# LED_Controller.net
KiCad netlist of a schematic drawn in Altium Designer
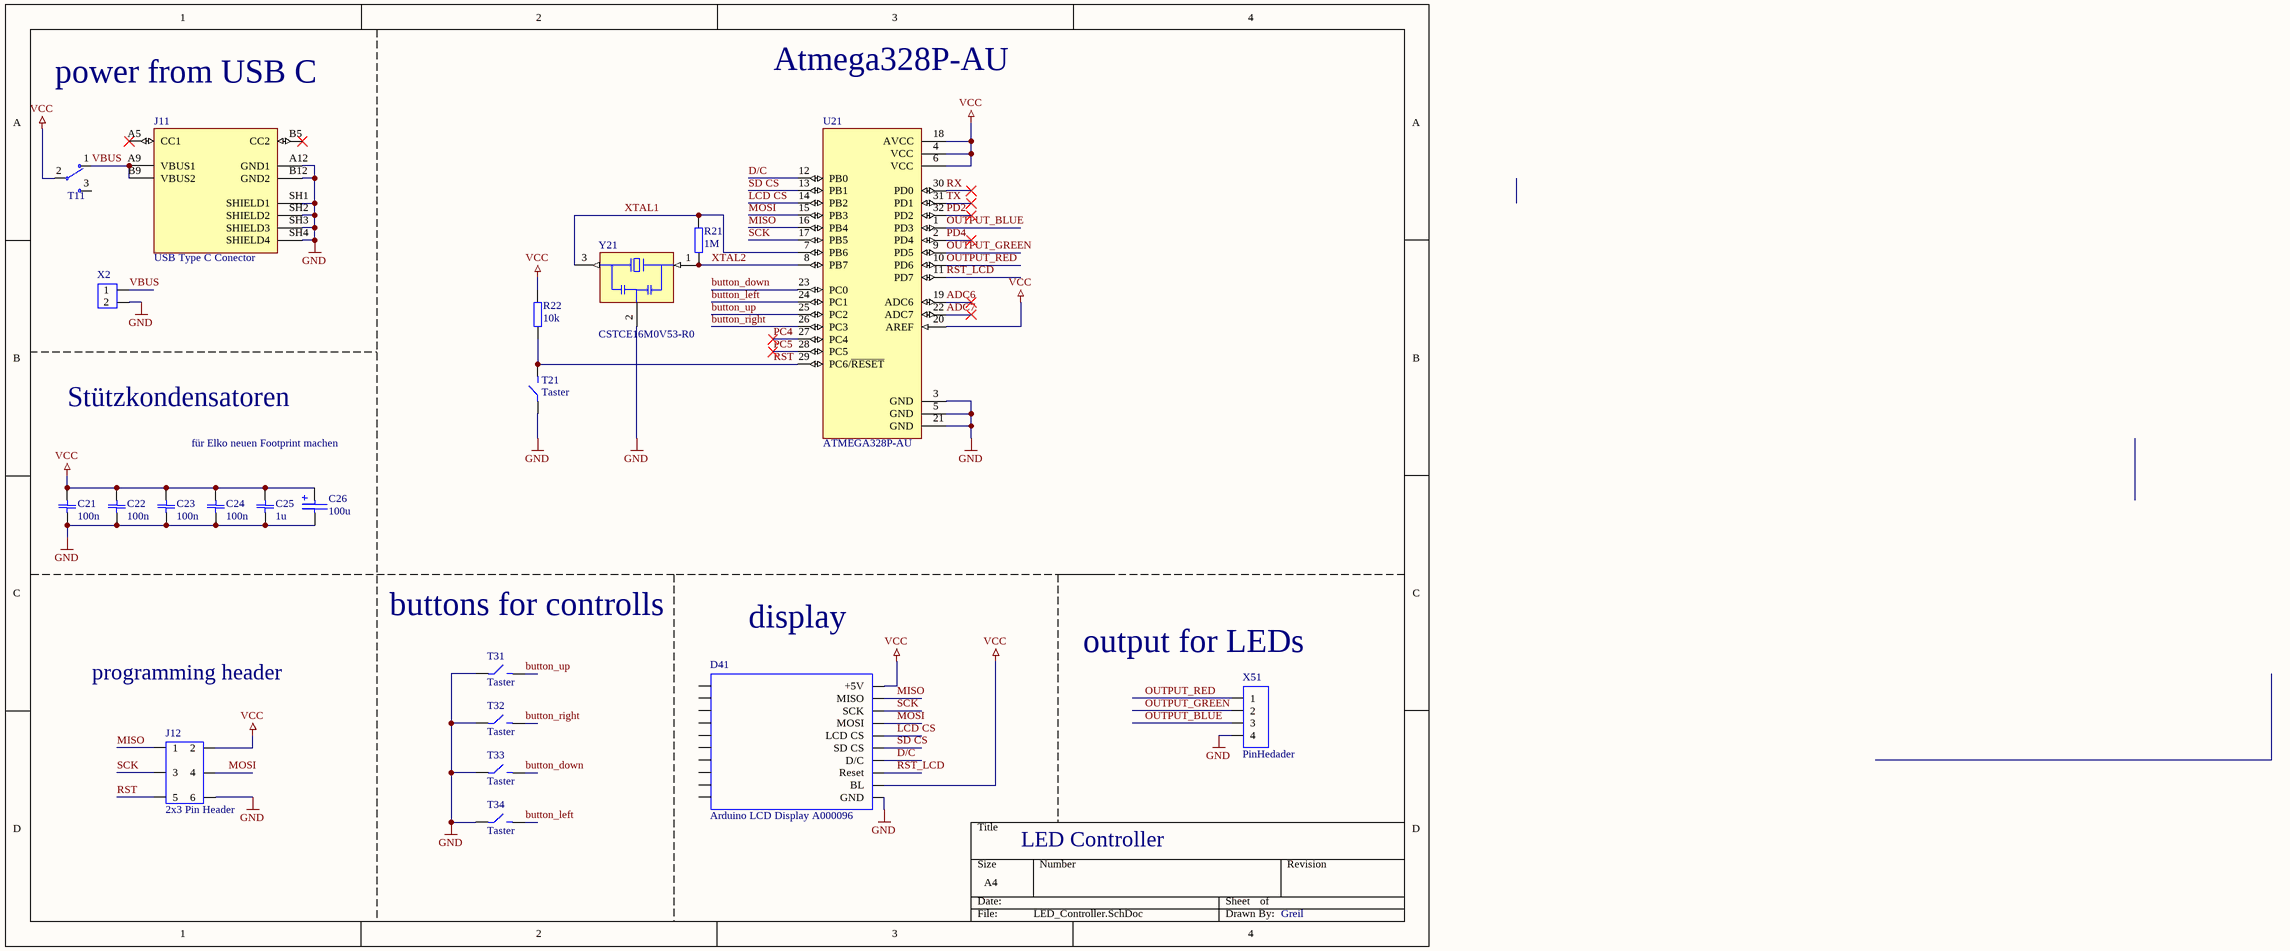
[diagram p0: LED_Controller.SchDoc]

(export (version "E")
  (design (tool "Eeschema 10.0.6"))
  (components
    (comp (ref "C21")
      (value "100n")
      (footprint "CAP0805")
      (fields (field (name "MP") "VJ1206A220GXCAP"))
      (libsource (lib "LED_Controller") (part "SMD CAP"))
    )
    (comp (ref "C22")
      (value "100n")
      (footprint "CAP0805")
      (fields (field (name "MP") "VJ1206A220GXCAP"))
      (libsource (lib "LED_Controller") (part "SMD CAP"))
    )
    (comp (ref "C23")
      (value "100n")
      (footprint "CAP0805")
      (fields (field (name "MP") "VJ1206A220GXCAP"))
      (libsource (lib "LED_Controller") (part "SMD CAP"))
    )
    (comp (ref "C24")
      (value "100n")
      (footprint "CAP0805")
      (fields (field (name "MP") "VJ1206A220GXCAP"))
      (libsource (lib "LED_Controller") (part "SMD CAP"))
    )
    (comp (ref "C25")
      (value "1u")
      (footprint "CAP0805")
      (fields (field (name "MP") "VJ1206A220GXCAP"))
      (libsource (lib "LED_Controller") (part "SMD CAP"))
    )
    (comp (ref "C26") (value "100u") (footprint "ELKO_D5.0") (libsource (lib "1BHELS_2_Greil") (part "ELKO")))
    (comp (ref "D41")
      (value "Arduino LCD Display A000096")
      (footprint "Arduino LCD Display A000096")
      (libsource (lib "1BHELS_2_Greil") (part "Arduino LCD Display A000096"))
    )
    (comp (ref "J11")
      (value "USB Type C Conector")
      (footprint "MOLEX_2171750001")
      (fields (field (name "MF") "Molex") (field (name "MP") "2171750001"))
      (libsource (lib "LED_Controller") (part "USB Type C Conector"))
    )
    (comp (ref "J12")
      (value "2x3 Pin Header")
      (footprint "2x3 Pin Header")
      (libsource (lib "LED_Controller") (part "2x3 Pin Header"))
    )
    (comp (ref "R21")
      (value "1M")
      (footprint "LED_Controller:RES_ERJU08J154V")
      (fields (field (name "MP") "ERJU08J154V"))
      (libsource (lib "LED_Controller") (part "Res 1206"))
    )
    (comp (ref "R22")
      (value "10k")
      (footprint "LED_Controller:RES_ERJU08J154V")
      (fields (field (name "MP") "ERJU08J154V"))
      (libsource (lib "LED_Controller") (part "Res 1206"))
    )
    (comp (ref "T11")
      (value "Toggel Switch")
      (footprint "Toggel Switch")
      (libsource (lib "LED_Controller") (part "Toggel Switch"))
    )
    (comp (ref "T21")
      (value "Taster")
      (footprint "Taster")
      (libsource (lib "1BHELS_2_Greil") (part "Taster"))
    )
    (comp (ref "T31")
      (value "Taster")
      (footprint "Taster")
      (libsource (lib "1BHELS_2_Greil") (part "Taster"))
    )
    (comp (ref "T32")
      (value "Taster")
      (footprint "Taster")
      (libsource (lib "1BHELS_2_Greil") (part "Taster"))
    )
    (comp (ref "T33")
      (value "Taster")
      (footprint "Taster")
      (libsource (lib "1BHELS_2_Greil") (part "Taster"))
    )
    (comp (ref "T34")
      (value "Taster")
      (footprint "Taster")
      (libsource (lib "1BHELS_2_Greil") (part "Taster"))
    )
    (comp (ref "U21")
      (value "ATMEGA328P-AU")
      (footprint "QFP80P900X900X120-32N")
      (description "AVR AVRÂ® ATmega Microcontroller IC 8-Bit 20MHz 32KB (16K x 16) FLASH 32-TQFP (7x7)")
      (fields (field (name "MF") "Microchip Technology"))
      (libsource (lib "LED_Controller") (part "ATMEGA328P-AU"))
    )
    (comp (ref "X2")
      (value "PinHedader")
      (footprint "CON2")
      (libsource (lib "1BHELS_2_Greil") (part "CON 2"))
    )
    (comp (ref "X51")
      (value "PinHedader")
      (footprint "CON4_200mil")
      (libsource (lib "1BHELS_2_Greil") (part "CON4"))
    )
    (comp (ref "Y21")
      (value "CSTCE16M0V53-R0")
      (footprint "OSC_CSTCE16M0V53-R0")
      (description "16 MHz Ceramic Resonator Built in Capacitor 15 pF Â±0.3% -20Â°C ~ 80Â°C Surface Mount")
      (fields (field (name "MF") "Murata"))
      (libsource (lib "LED_Controller") (part "CSTCE16M0V53-R0"))
    )
  )
  (nets
    (net (code "1") (name "/ADC6") (class "Default")
      (node (ref "U21") (pin "19") (pinfunction "ADC6_19") (pintype "bidirectional+no_connect"))
    )
    (net (code "2") (name "/ADC7") (class "Default")
      (node (ref "U21") (pin "22") (pinfunction "ADC7_22") (pintype "bidirectional+no_connect"))
    )
    (net (code "3") (name "/D{slash}C") (class "Default")
      (node (ref "D41") (pin "D/C") (pinfunction "D/C_D/C") (pintype "passive"))
      (node (ref "U21") (pin "12") (pinfunction "PB0_12") (pintype "bidirectional"))
    )
    (net (code "4") (name "/LCD CS") (class "Default")
      (node (ref "D41") (pin "LCD_CS") (pinfunction "LCD_CS_LCD_CS") (pintype "passive"))
      (node (ref "U21") (pin "14") (pinfunction "PB2_14") (pintype "bidirectional"))
    )
    (net (code "5") (name "/MISO") (class "Default")
      (node (ref "D41") (pin "MISO") (pinfunction "MISO_MISO") (pintype "passive"))
      (node (ref "J12") (pin "1") (pinfunction "1_1") (pintype "passive"))
      (node (ref "U21") (pin "16") (pinfunction "PB4_16") (pintype "bidirectional"))
    )
    (net (code "6") (name "/MOSI") (class "Default")
      (node (ref "D41") (pin "MOSI") (pinfunction "MOSI_MOSI") (pintype "passive"))
      (node (ref "J12") (pin "4") (pinfunction "4_4") (pintype "passive"))
      (node (ref "U21") (pin "15") (pinfunction "PB3_15") (pintype "bidirectional"))
    )
    (net (code "7") (name "/OUTPUT_BLUE") (class "Default")
      (node (ref "U21") (pin "1") (pinfunction "PD3_1") (pintype "bidirectional"))
      (node (ref "X51") (pin "3") (pinfunction "3_3") (pintype "passive"))
    )
    (net (code "8") (name "/OUTPUT_GREEN") (class "Default")
      (node (ref "U21") (pin "9") (pinfunction "PD5_9") (pintype "bidirectional"))
      (node (ref "X51") (pin "2") (pinfunction "2_2") (pintype "passive"))
    )
    (net (code "9") (name "/OUTPUT_RED") (class "Default")
      (node (ref "U21") (pin "10") (pinfunction "PD6_10") (pintype "bidirectional"))
      (node (ref "X51") (pin "1") (pinfunction "1_1") (pintype "passive"))
    )
    (net (code "10") (name "/PC4") (class "Default")
      (node (ref "U21") (pin "27") (pinfunction "PC4_27") (pintype "bidirectional+no_connect"))
    )
    (net (code "11") (name "/PC5") (class "Default")
      (node (ref "U21") (pin "28") (pinfunction "PC5_28") (pintype "bidirectional+no_connect"))
    )
    (net (code "12") (name "/PD2") (class "Default")
      (node (ref "U21") (pin "32") (pinfunction "PD2_32") (pintype "bidirectional+no_connect"))
    )
    (net (code "13") (name "/PD4") (class "Default")
      (node (ref "U21") (pin "2") (pinfunction "PD4_2") (pintype "bidirectional+no_connect"))
    )
    (net (code "14") (name "/RST") (class "Default")
      (node (ref "J12") (pin "5") (pinfunction "5_5") (pintype "passive"))
      (node (ref "R22") (pin "1") (pinfunction "1_1") (pintype "passive"))
      (node (ref "T21") (pin "2") (pinfunction "2_2") (pintype "passive"))
      (node (ref "U21") (pin "29") (pinfunction "PC6/~{RESET}_29") (pintype "bidirectional"))
    )
    (net (code "15") (name "/RST_LCD") (class "Default")
      (node (ref "D41") (pin "Reset") (pinfunction "Reset_Reset") (pintype "passive"))
      (node (ref "U21") (pin "11") (pinfunction "PD7_11") (pintype "bidirectional"))
    )
    (net (code "16") (name "/RX") (class "Default")
      (node (ref "U21") (pin "30") (pinfunction "PD0_30") (pintype "bidirectional+no_connect"))
    )
    (net (code "17") (name "/SCK") (class "Default")
      (node (ref "D41") (pin "SCK") (pinfunction "SCK_SCK") (pintype "passive"))
      (node (ref "J12") (pin "3") (pinfunction "3_3") (pintype "passive"))
      (node (ref "U21") (pin "17") (pinfunction "PB5_17") (pintype "bidirectional"))
    )
    (net (code "18") (name "/SD CS") (class "Default")
      (node (ref "D41") (pin "SD_CS") (pinfunction "SD_CS_SD_CS") (pintype "passive"))
      (node (ref "U21") (pin "13") (pinfunction "PB1_13") (pintype "bidirectional"))
    )
    (net (code "19") (name "/TX") (class "Default")
      (node (ref "U21") (pin "31") (pinfunction "PD1_31") (pintype "bidirectional+no_connect"))
    )
    (net (code "20") (name "/VBUS") (class "Default")
      (node (ref "J11") (pin "A9") (pinfunction "VBUS1_A9") (pintype "power_in"))
      (node (ref "J11") (pin "B9") (pinfunction "VBUS2_B9") (pintype "power_in"))
      (node (ref "T11") (pin "1") (pinfunction "1_1") (pintype "passive"))
      (node (ref "X2") (pin "1") (pinfunction "1_1") (pintype "passive"))
    )
    (net (code "21") (name "/XTAL1") (class "Default")
      (node (ref "R21") (pin "2") (pinfunction "2_2") (pintype "passive"))
      (node (ref "U21") (pin "7") (pinfunction "PB6_7") (pintype "bidirectional"))
      (node (ref "Y21") (pin "3") (pinfunction "OUT_3") (pintype "output"))
    )
    (net (code "22") (name "/XTAL2") (class "Default")
      (node (ref "R21") (pin "1") (pinfunction "1_1") (pintype "passive"))
      (node (ref "U21") (pin "8") (pinfunction "PB7_8") (pintype "bidirectional"))
      (node (ref "Y21") (pin "1") (pinfunction "IN_1") (pintype "input"))
    )
    (net (code "23") (name "/button_down") (class "Default")
      (node (ref "T33") (pin "2") (pinfunction "2_2") (pintype "passive"))
      (node (ref "U21") (pin "23") (pinfunction "PC0_23") (pintype "bidirectional"))
    )
    (net (code "24") (name "/button_left") (class "Default")
      (node (ref "T34") (pin "2") (pinfunction "2_2") (pintype "passive"))
      (node (ref "U21") (pin "24") (pinfunction "PC1_24") (pintype "bidirectional"))
    )
    (net (code "25") (name "/button_right") (class "Default")
      (node (ref "T32") (pin "2") (pinfunction "2_2") (pintype "passive"))
      (node (ref "U21") (pin "26") (pinfunction "PC3_26") (pintype "bidirectional"))
    )
    (net (code "26") (name "/button_up") (class "Default")
      (node (ref "T31") (pin "2") (pinfunction "2_2") (pintype "passive"))
      (node (ref "U21") (pin "25") (pinfunction "PC2_25") (pintype "bidirectional"))
    )
    (net (code "27") (name "GND") (class "Default")
      (node (ref "C21") (pin "1") (pinfunction "1_1") (pintype "passive"))
      (node (ref "C22") (pin "1") (pinfunction "1_1") (pintype "passive"))
      (node (ref "C23") (pin "1") (pinfunction "1_1") (pintype "passive"))
      (node (ref "C24") (pin "1") (pinfunction "1_1") (pintype "passive"))
      (node (ref "C25") (pin "1") (pinfunction "1_1") (pintype "passive"))
      (node (ref "C26") (pin "N") (pinfunction "N_N") (pintype "passive"))
      (node (ref "D41") (pin "GND") (pinfunction "GND_GND") (pintype "passive"))
      (node (ref "J11") (pin "A12") (pinfunction "GND1_A12") (pintype "power_in"))
      (node (ref "J11") (pin "B12") (pinfunction "GND2_B12") (pintype "power_in"))
      (node (ref "J11") (pin "SH1") (pinfunction "SHIELD1_SH1") (pintype "passive"))
      (node (ref "J11") (pin "SH2") (pinfunction "SHIELD2_SH2") (pintype "passive"))
      (node (ref "J11") (pin "SH3") (pinfunction "SHIELD3_SH3") (pintype "passive"))
      (node (ref "J11") (pin "SH4") (pinfunction "SHIELD4_SH4") (pintype "passive"))
      (node (ref "J12") (pin "6") (pinfunction "6_6") (pintype "passive"))
      (node (ref "T21") (pin "1") (pinfunction "1_1") (pintype "passive"))
      (node (ref "T31") (pin "1") (pinfunction "1_1") (pintype "passive"))
      (node (ref "T32") (pin "1") (pinfunction "1_1") (pintype "passive"))
      (node (ref "T33") (pin "1") (pinfunction "1_1") (pintype "passive"))
      (node (ref "T34") (pin "1") (pinfunction "1_1") (pintype "passive"))
      (node (ref "U21") (pin "21") (pinfunction "GND_21") (pintype "power_in"))
      (node (ref "U21") (pin "3") (pinfunction "GND_3") (pintype "power_in"))
      (node (ref "U21") (pin "5") (pinfunction "GND_5") (pintype "power_in"))
      (node (ref "X2") (pin "2") (pinfunction "2_2") (pintype "passive"))
      (node (ref "X51") (pin "4") (pinfunction "4_4") (pintype "passive"))
      (node (ref "Y21") (pin "2") (pinfunction "GND_2") (pintype "power_in"))
    )
    (net (code "28") (name "VCC") (class "Default")
      (node (ref "C21") (pin "2") (pinfunction "2_2") (pintype "passive"))
      (node (ref "C22") (pin "2") (pinfunction "2_2") (pintype "passive"))
      (node (ref "C23") (pin "2") (pinfunction "2_2") (pintype "passive"))
      (node (ref "C24") (pin "2") (pinfunction "2_2") (pintype "passive"))
      (node (ref "C25") (pin "2") (pinfunction "2_2") (pintype "passive"))
      (node (ref "C26") (pin "P") (pinfunction "P_P") (pintype "passive"))
      (node (ref "D41") (pin "+5V") (pinfunction "+5V_+5V") (pintype "passive"))
      (node (ref "D41") (pin "BL") (pinfunction "BL_BL") (pintype "passive"))
      (node (ref "J12") (pin "2") (pinfunction "2_2") (pintype "passive"))
      (node (ref "R22") (pin "2") (pinfunction "2_2") (pintype "passive"))
      (node (ref "T11") (pin "2") (pinfunction "2_2") (pintype "passive"))
      (node (ref "U21") (pin "18") (pinfunction "AVCC_18") (pintype "power_in"))
      (node (ref "U21") (pin "20") (pinfunction "AREF_20") (pintype "input"))
      (node (ref "U21") (pin "4") (pinfunction "VCC_4") (pintype "power_in"))
      (node (ref "U21") (pin "6") (pinfunction "VCC_6") (pintype "power_in"))
    )
    (net (code "29") (name "unconnected-(D41-Pad1)") (class "Default")
      (node (ref "D41") (pin "1") (pinfunction "1_1") (pintype "passive"))
    )
    (net (code "30") (name "unconnected-(D41-Pad2)") (class "Default")
      (node (ref "D41") (pin "2") (pinfunction "2_2") (pintype "passive"))
    )
    (net (code "31") (name "unconnected-(D41-Pad3)") (class "Default")
      (node (ref "D41") (pin "3") (pinfunction "3_3") (pintype "passive"))
    )
    (net (code "32") (name "unconnected-(D41-Pad4)") (class "Default")
      (node (ref "D41") (pin "4") (pinfunction "4_4") (pintype "passive"))
    )
    (net (code "33") (name "unconnected-(D41-Pad5)") (class "Default")
      (node (ref "D41") (pin "5") (pinfunction "5_5") (pintype "passive"))
    )
    (net (code "34") (name "unconnected-(D41-Pad6)") (class "Default")
      (node (ref "D41") (pin "6") (pinfunction "6_6") (pintype "passive"))
    )
    (net (code "35") (name "unconnected-(D41-Pad7)") (class "Default")
      (node (ref "D41") (pin "7") (pinfunction "7_7") (pintype "passive"))
    )
    (net (code "36") (name "unconnected-(D41-Pad8)") (class "Default")
      (node (ref "D41") (pin "8") (pinfunction "8_8") (pintype "passive"))
    )
    (net (code "37") (name "unconnected-(D41-Pad9)") (class "Default")
      (node (ref "D41") (pin "9") (pinfunction "9_9") (pintype "passive"))
    )
    (net (code "38") (name "unconnected-(D41-Pad10)") (class "Default")
      (node (ref "D41") (pin "10") (pinfunction "10_10") (pintype "passive"))
    )
    (net (code "39") (name "unconnected-(J11-CC1-PadA5)") (class "Default")
      (node (ref "J11") (pin "A5") (pinfunction "CC1_A5") (pintype "bidirectional+no_connect"))
    )
    (net (code "40") (name "unconnected-(J11-CC2-PadB5)") (class "Default")
      (node (ref "J11") (pin "B5") (pinfunction "CC2_B5") (pintype "bidirectional+no_connect"))
    )
    (net (code "41") (name "unconnected-(T11-Pad3)") (class "Default")
      (node (ref "T11") (pin "3") (pinfunction "3_3") (pintype "passive"))
    )
  )
)
